# temp_mon_with_eeprom_rev_1.net
KiCad netlist of a schematic drawn in EAGLE
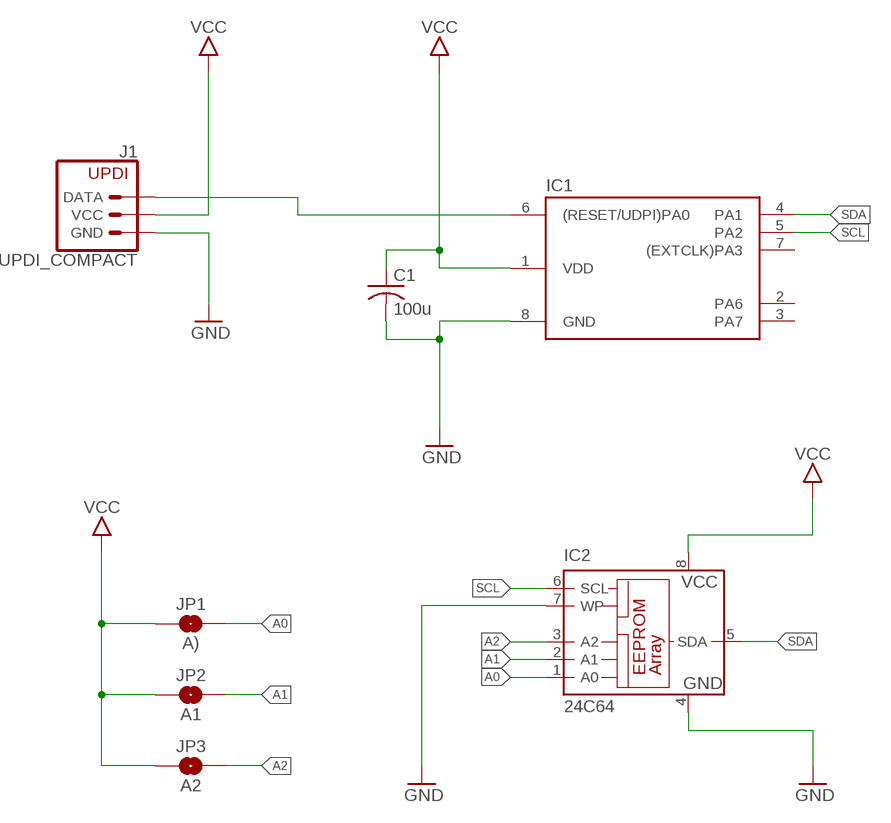
[diagram p0: schematic, sheet 1]

(export (version "E")
  (design (tool "Eeschema 10.0.6"))
  (components
    (comp (ref "C1")
      (value "100u")
      (footprint "eagle-import:C0603")
      (libsource (lib "eagle-import") (part "C-USC0603"))
    )
    (comp (ref "IC1")
      (value "ATTINY212/412")
      (footprint "eagle-import:SOIC8N")
      (libsource (lib "eagle-import") (part "ATTINY212/412"))
    )
    (comp (ref "IC2")
      (value "24C64")
      (footprint "eagle-import:SO-08")
      (libsource (lib "eagle-import") (part "24CSN04C"))
    )
    (comp (ref "J1")
      (value "UPDI_COMPACT")
      (footprint "eagle-import:UPDI_1X3")
      (libsource (lib "eagle-import") (part "UPDI_COMPACT"))
    )
    (comp (ref "JP1")
      (value "A)")
      (footprint "eagle-import:SMT-JUMPER_2_NO_SILK")
      (libsource (lib "eagle-import") (part "JUMPER-SMT_2_NO_SILK"))
    )
    (comp (ref "JP2")
      (value "A1")
      (footprint "eagle-import:SMT-JUMPER_2_NO_SILK")
      (libsource (lib "eagle-import") (part "JUMPER-SMT_2_NO_SILK"))
    )
    (comp (ref "JP3")
      (value "A2")
      (footprint "eagle-import:SMT-JUMPER_2_NO_SILK")
      (libsource (lib "eagle-import") (part "JUMPER-SMT_2_NO_SILK"))
    )
  )
  (nets
    (net (code "1") (name "A0") (class "Default")
      (node (ref "IC2") (pin "1") (pinfunction "A0_1") (pintype "input"))
      (node (ref "JP1") (pin "2") (pinfunction "2_2") (pintype "passive"))
    )
    (net (code "2") (name "A1") (class "Default")
      (node (ref "IC2") (pin "2") (pinfunction "A1_2") (pintype "input"))
      (node (ref "JP2") (pin "2") (pinfunction "2_2") (pintype "passive"))
    )
    (net (code "3") (name "A2") (class "Default")
      (node (ref "IC2") (pin "3") (pinfunction "A2_3") (pintype "input"))
      (node (ref "JP3") (pin "2") (pinfunction "2_2") (pintype "passive"))
    )
    (net (code "4") (name "GND") (class "Default")
      (node (ref "C1") (pin "2") (pinfunction "2_2") (pintype "passive"))
      (node (ref "IC1") (pin "8") (pinfunction "GND_8") (pintype "power_in"))
      (node (ref "IC2") (pin "4") (pinfunction "GND_4") (pintype "power_in"))
      (node (ref "IC2") (pin "7") (pinfunction "WP_7") (pintype "input"))
      (node (ref "J1") (pin "2") (pinfunction "GND_2") (pintype "power_in"))
    )
    (net (code "5") (name "Net-(IC1-(RESET{slash}UDPI)PA0)") (class "Default")
      (node (ref "IC1") (pin "6") (pinfunction "(RESET/UDPI)PA0_6") (pintype "bidirectional"))
      (node (ref "J1") (pin "3") (pinfunction "DATA_3") (pintype "bidirectional"))
    )
    (net (code "6") (name "SCL") (class "Default")
      (node (ref "IC1") (pin "5") (pinfunction "PA2_5") (pintype "bidirectional"))
      (node (ref "IC2") (pin "6") (pinfunction "SCL_6") (pintype "input"))
    )
    (net (code "7") (name "SDA") (class "Default")
      (node (ref "IC1") (pin "4") (pinfunction "PA1_4") (pintype "bidirectional"))
      (node (ref "IC2") (pin "5") (pinfunction "SDA_5") (pintype "bidirectional"))
    )
    (net (code "8") (name "VCC") (class "Default")
      (node (ref "C1") (pin "1") (pinfunction "1_1") (pintype "passive"))
      (node (ref "IC1") (pin "1") (pinfunction "VDD_1") (pintype "power_in"))
      (node (ref "IC2") (pin "8") (pinfunction "VCC_8") (pintype "power_in"))
      (node (ref "J1") (pin "1") (pinfunction "VCC_1") (pintype "power_in"))
      (node (ref "JP1") (pin "1") (pinfunction "1_1") (pintype "passive"))
      (node (ref "JP2") (pin "1") (pinfunction "1_1") (pintype "passive"))
      (node (ref "JP3") (pin "1") (pinfunction "1_1") (pintype "passive"))
    )
    (net (code "9") (name "unconnected-(IC1-(EXTCLK)PA3-Pad7)") (class "Default")
      (node (ref "IC1") (pin "7") (pinfunction "(EXTCLK)PA3_7") (pintype "bidirectional"))
    )
    (net (code "10") (name "unconnected-(IC1-PA6-Pad2)") (class "Default")
      (node (ref "IC1") (pin "2") (pinfunction "PA6_2") (pintype "bidirectional"))
    )
    (net (code "11") (name "unconnected-(IC1-PA7-Pad3)") (class "Default")
      (node (ref "IC1") (pin "3") (pinfunction "PA7_3") (pintype "bidirectional"))
    )
  )
)
